# usb-hub-v0_3.net
KiCad netlist of a schematic drawn in EAGLE
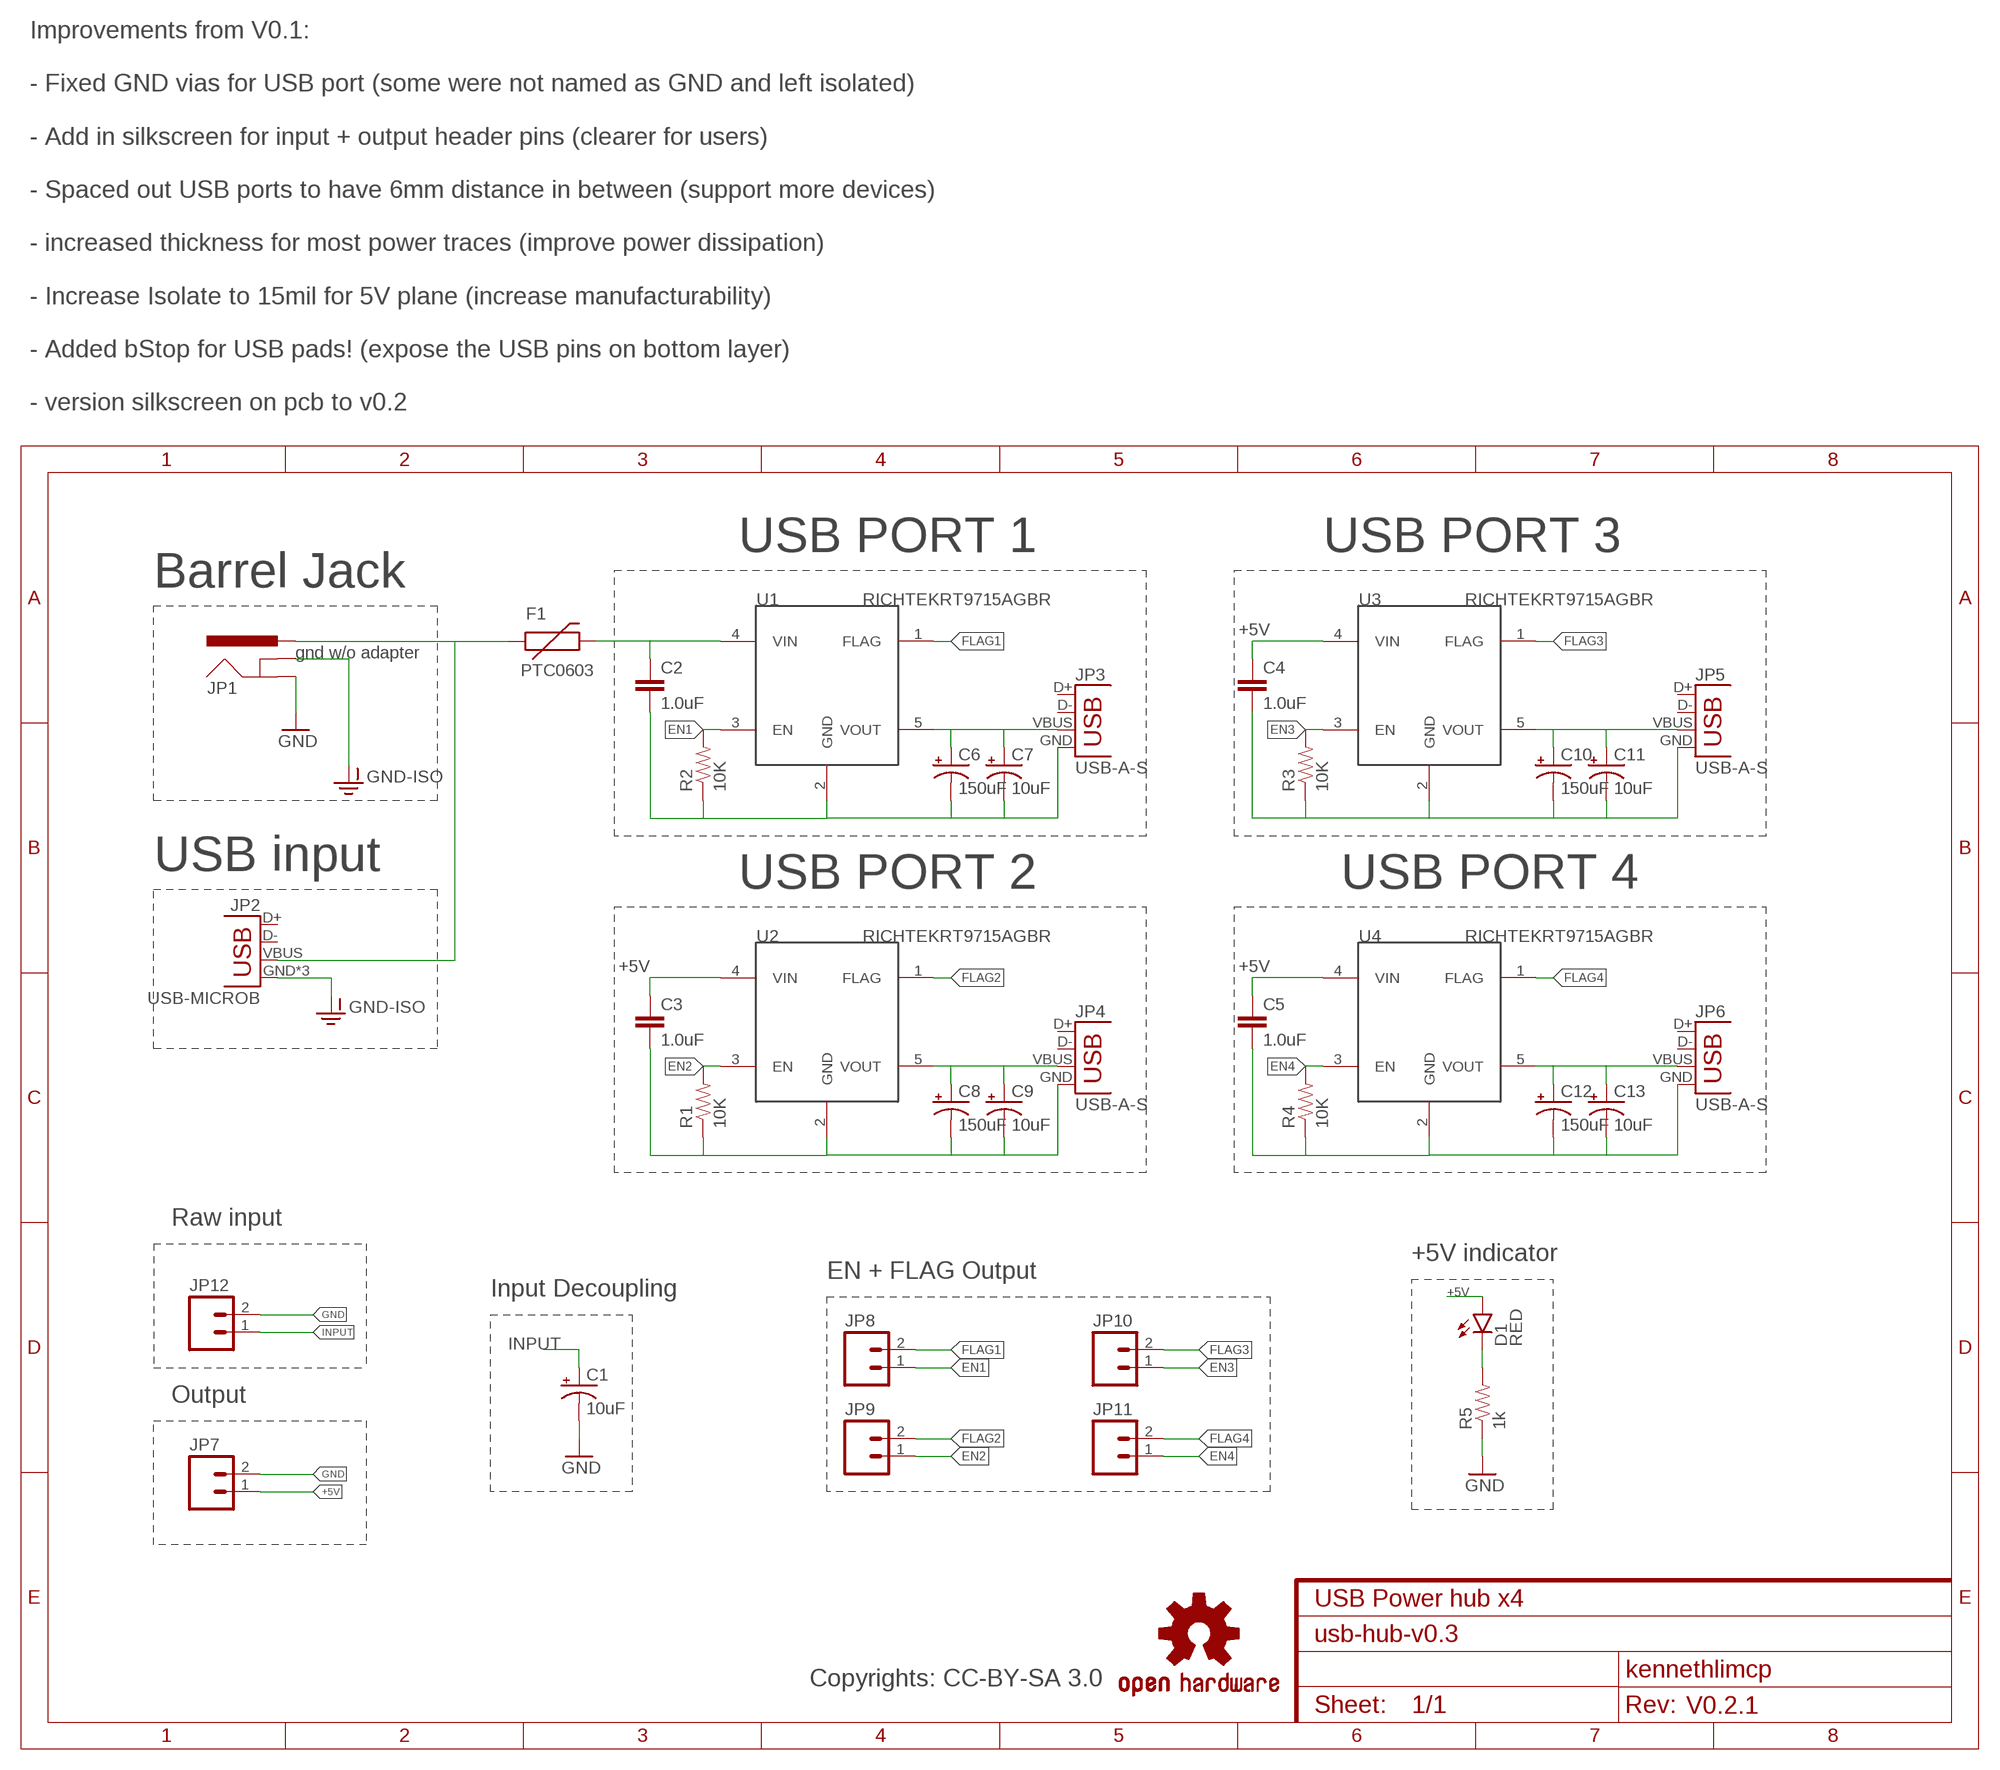
[diagram p0: schematic, sheet 1]

(export (version "E")
  (design (tool "Eeschema 10.0.6"))
  (components
    (comp (ref "C1")
      (value "10uF")
      (footprint "eagle-import:EIA3216")
      (libsource (lib "eagle-import") (part "10UF-16V-10%(TANT)"))
    )
    (comp (ref "C2")
      (value "1.0uF")
      (footprint "eagle-import:0603-CAP")
      (libsource (lib "eagle-import") (part "1.0UF-16V-10%(0603)"))
    )
    (comp (ref "C3")
      (value "1.0uF")
      (footprint "eagle-import:0603-CAP")
      (libsource (lib "eagle-import") (part "1.0UF-16V-10%(0603)"))
    )
    (comp (ref "C4")
      (value "1.0uF")
      (footprint "eagle-import:0603-CAP")
      (libsource (lib "eagle-import") (part "1.0UF-16V-10%(0603)"))
    )
    (comp (ref "C5")
      (value "1.0uF")
      (footprint "eagle-import:0603-CAP")
      (libsource (lib "eagle-import") (part "1.0UF-16V-10%(0603)"))
    )
    (comp (ref "C6")
      (value "150uF")
      (footprint "eagle-import:PANASONIC_D")
      (libsource (lib "eagle-import") (part "CAP_POLD"))
    )
    (comp (ref "C7")
      (value "10uF")
      (footprint "eagle-import:EIA3216")
      (libsource (lib "eagle-import") (part "10UF-16V-10%(TANT)"))
    )
    (comp (ref "C8")
      (value "150uF")
      (footprint "eagle-import:PANASONIC_D")
      (libsource (lib "eagle-import") (part "CAP_POLD"))
    )
    (comp (ref "C9")
      (value "10uF")
      (footprint "eagle-import:EIA3216")
      (libsource (lib "eagle-import") (part "10UF-16V-10%(TANT)"))
    )
    (comp (ref "C10")
      (value "150uF")
      (footprint "eagle-import:PANASONIC_D")
      (libsource (lib "eagle-import") (part "CAP_POLD"))
    )
    (comp (ref "C11")
      (value "10uF")
      (footprint "eagle-import:EIA3216")
      (libsource (lib "eagle-import") (part "10UF-16V-10%(TANT)"))
    )
    (comp (ref "C12")
      (value "150uF")
      (footprint "eagle-import:PANASONIC_D")
      (libsource (lib "eagle-import") (part "CAP_POLD"))
    )
    (comp (ref "C13")
      (value "10uF")
      (footprint "eagle-import:EIA3216")
      (libsource (lib "eagle-import") (part "10UF-16V-10%(TANT)"))
    )
    (comp (ref "D1")
      (value "RED")
      (footprint "eagle-import:LED-0603")
      (libsource (lib "eagle-import") (part "LED-RED0603"))
    )
    (comp (ref "F1")
      (value "PTC0603")
      (footprint "eagle-import:0603")
      (libsource (lib "eagle-import") (part "PTC0603"))
    )
    (comp (ref "JP1")
      (value "POWER_JACKPTH_LOCK")
      (footprint "eagle-import:POWER_JACK_PTH_LOCK")
      (libsource (lib "eagle-import") (part "POWER_JACKPTH_LOCK"))
    )
    (comp (ref "JP2")
      (value "USB-MICROB")
      (footprint "eagle-import:USB-MICROB")
      (libsource (lib "eagle-import") (part "USB-MICROB"))
    )
    (comp (ref "JP3")
      (value "USB-A-S")
      (footprint "eagle-import:USB-A-S")
      (libsource (lib "eagle-import") (part "USB-A-S"))
    )
    (comp (ref "JP4")
      (value "USB-A-S")
      (footprint "eagle-import:USB-A-S")
      (libsource (lib "eagle-import") (part "USB-A-S"))
    )
    (comp (ref "JP5")
      (value "USB-A-S")
      (footprint "eagle-import:USB-A-S")
      (libsource (lib "eagle-import") (part "USB-A-S"))
    )
    (comp (ref "JP6")
      (value "USB-A-S")
      (footprint "eagle-import:USB-A-S")
      (libsource (lib "eagle-import") (part "USB-A-S"))
    )
    (comp (ref "JP7")
      (value "M02PTH")
      (footprint "eagle-import:1X02")
      (libsource (lib "eagle-import") (part "M02PTH"))
    )
    (comp (ref "JP8")
      (value "M02PTH")
      (footprint "eagle-import:1X02")
      (libsource (lib "eagle-import") (part "M02PTH"))
    )
    (comp (ref "JP9")
      (value "M02PTH")
      (footprint "eagle-import:1X02")
      (libsource (lib "eagle-import") (part "M02PTH"))
    )
    (comp (ref "JP10")
      (value "M02PTH")
      (footprint "eagle-import:1X02")
      (libsource (lib "eagle-import") (part "M02PTH"))
    )
    (comp (ref "JP11")
      (value "M02PTH")
      (footprint "eagle-import:1X02")
      (libsource (lib "eagle-import") (part "M02PTH"))
    )
    (comp (ref "JP12")
      (value "M02PTH")
      (footprint "eagle-import:1X02")
      (libsource (lib "eagle-import") (part "M02PTH"))
    )
    (comp (ref "LOGO1")
      (value "OSHW-LOGOPAD")
      (footprint "eagle-import:OSHW-LOGO-M-PAD")
      (libsource (lib "eagle-import") (part "OSHW-LOGOPAD"))
    )
    (comp (ref "R1")
      (value "10K")
      (footprint "eagle-import:0402-RES")
      (libsource (lib "eagle-import") (part "RESISTOR0402"))
    )
    (comp (ref "R2")
      (value "10K")
      (footprint "eagle-import:0402-RES")
      (libsource (lib "eagle-import") (part "RESISTOR0402"))
    )
    (comp (ref "R3")
      (value "10K")
      (footprint "eagle-import:0402-RES")
      (libsource (lib "eagle-import") (part "RESISTOR0402"))
    )
    (comp (ref "R4")
      (value "10K")
      (footprint "eagle-import:0402-RES")
      (libsource (lib "eagle-import") (part "RESISTOR0402"))
    )
    (comp (ref "R5")
      (value "1k")
      (footprint "eagle-import:0402-RES")
      (libsource (lib "eagle-import") (part "RESISTOR0402"))
    )
    (comp (ref "U1")
      (value "RICHTEKRT9715AGBR")
      (footprint "eagle-import:SOT23-5")
      (libsource (lib "eagle-import") (part "RICHTEKRT9715AGBR"))
    )
    (comp (ref "U2")
      (value "RICHTEKRT9715AGBR")
      (footprint "eagle-import:SOT23-5")
      (libsource (lib "eagle-import") (part "RICHTEKRT9715AGBR"))
    )
    (comp (ref "U3")
      (value "RICHTEKRT9715AGBR")
      (footprint "eagle-import:SOT23-5")
      (libsource (lib "eagle-import") (part "RICHTEKRT9715AGBR"))
    )
    (comp (ref "U4")
      (value "RICHTEKRT9715AGBR")
      (footprint "eagle-import:SOT23-5")
      (libsource (lib "eagle-import") (part "RICHTEKRT9715AGBR"))
    )
  )
  (nets
    (net (code "1") (name "+5V") (class "Default")
      (node (ref "C2") (pin "1") (pinfunction "1_1") (pintype "passive"))
      (node (ref "C3") (pin "1") (pinfunction "1_1") (pintype "passive"))
      (node (ref "C4") (pin "1") (pinfunction "1_1") (pintype "passive"))
      (node (ref "C5") (pin "1") (pinfunction "1_1") (pintype "passive"))
      (node (ref "D1") (pin "A") (pinfunction "A_A") (pintype "passive"))
      (node (ref "F1") (pin "2") (pinfunction "2_2") (pintype "bidirectional"))
      (node (ref "JP7") (pin "1") (pinfunction "1_1") (pintype "passive"))
      (node (ref "U1") (pin "4") (pinfunction "VIN_4") (pintype "bidirectional"))
      (node (ref "U2") (pin "4") (pinfunction "VIN_4") (pintype "bidirectional"))
      (node (ref "U3") (pin "4") (pinfunction "VIN_4") (pintype "bidirectional"))
      (node (ref "U4") (pin "4") (pinfunction "VIN_4") (pintype "bidirectional"))
    )
    (net (code "2") (name "EN1") (class "Default")
      (node (ref "JP8") (pin "1") (pinfunction "1_1") (pintype "passive"))
      (node (ref "R2") (pin "2") (pinfunction "2_2") (pintype "passive"))
      (node (ref "U1") (pin "3") (pinfunction "EN_3") (pintype "bidirectional"))
    )
    (net (code "3") (name "EN2") (class "Default")
      (node (ref "JP9") (pin "1") (pinfunction "1_1") (pintype "passive"))
      (node (ref "R1") (pin "2") (pinfunction "2_2") (pintype "passive"))
      (node (ref "U2") (pin "3") (pinfunction "EN_3") (pintype "bidirectional"))
    )
    (net (code "4") (name "EN3") (class "Default")
      (node (ref "JP10") (pin "1") (pinfunction "1_1") (pintype "passive"))
      (node (ref "R3") (pin "2") (pinfunction "2_2") (pintype "passive"))
      (node (ref "U3") (pin "3") (pinfunction "EN_3") (pintype "bidirectional"))
    )
    (net (code "5") (name "EN4") (class "Default")
      (node (ref "JP11") (pin "1") (pinfunction "1_1") (pintype "passive"))
      (node (ref "R4") (pin "2") (pinfunction "2_2") (pintype "passive"))
      (node (ref "U4") (pin "3") (pinfunction "EN_3") (pintype "bidirectional"))
    )
    (net (code "6") (name "FLAG1") (class "Default")
      (node (ref "JP8") (pin "2") (pinfunction "2_2") (pintype "passive"))
      (node (ref "U1") (pin "1") (pinfunction "FLAG_1") (pintype "bidirectional"))
    )
    (net (code "7") (name "FLAG2") (class "Default")
      (node (ref "JP9") (pin "2") (pinfunction "2_2") (pintype "passive"))
      (node (ref "U2") (pin "1") (pinfunction "FLAG_1") (pintype "bidirectional"))
    )
    (net (code "8") (name "FLAG3") (class "Default")
      (node (ref "JP10") (pin "2") (pinfunction "2_2") (pintype "passive"))
      (node (ref "U3") (pin "1") (pinfunction "FLAG_1") (pintype "bidirectional"))
    )
    (net (code "9") (name "FLAG4") (class "Default")
      (node (ref "JP11") (pin "2") (pinfunction "2_2") (pintype "passive"))
      (node (ref "U4") (pin "1") (pinfunction "FLAG_1") (pintype "bidirectional"))
    )
    (net (code "10") (name "GND") (class "Default")
      (node (ref "C1") (pin "C") (pinfunction "-_C") (pintype "passive"))
      (node (ref "C10") (pin "-") (pinfunction "-_-") (pintype "passive"))
      (node (ref "C11") (pin "C") (pinfunction "-_C") (pintype "passive"))
      (node (ref "C12") (pin "-") (pinfunction "-_-") (pintype "passive"))
      (node (ref "C13") (pin "C") (pinfunction "-_C") (pintype "passive"))
      (node (ref "C2") (pin "2") (pinfunction "2_2") (pintype "passive"))
      (node (ref "C3") (pin "2") (pinfunction "2_2") (pintype "passive"))
      (node (ref "C4") (pin "2") (pinfunction "2_2") (pintype "passive"))
      (node (ref "C5") (pin "2") (pinfunction "2_2") (pintype "passive"))
      (node (ref "C6") (pin "-") (pinfunction "-_-") (pintype "passive"))
      (node (ref "C7") (pin "C") (pinfunction "-_C") (pintype "passive"))
      (node (ref "C8") (pin "-") (pinfunction "-_-") (pintype "passive"))
      (node (ref "C9") (pin "C") (pinfunction "-_C") (pintype "passive"))
      (node (ref "JP1") (pin "GND") (pinfunction "GND_GND") (pintype "bidirectional"))
      (node (ref "JP12") (pin "2") (pinfunction "2_2") (pintype "passive"))
      (node (ref "JP3") (pin "GND") (pinfunction "GND_GND") (pintype "bidirectional"))
      (node (ref "JP4") (pin "GND") (pinfunction "GND_GND") (pintype "bidirectional"))
      (node (ref "JP5") (pin "GND") (pinfunction "GND_GND") (pintype "bidirectional"))
      (node (ref "JP6") (pin "GND") (pinfunction "GND_GND") (pintype "bidirectional"))
      (node (ref "JP7") (pin "2") (pinfunction "2_2") (pintype "passive"))
      (node (ref "R1") (pin "1") (pinfunction "1_1") (pintype "passive"))
      (node (ref "R2") (pin "1") (pinfunction "1_1") (pintype "passive"))
      (node (ref "R3") (pin "1") (pinfunction "1_1") (pintype "passive"))
      (node (ref "R4") (pin "1") (pinfunction "1_1") (pintype "passive"))
      (node (ref "R5") (pin "1") (pinfunction "1_1") (pintype "passive"))
      (node (ref "U1") (pin "2") (pinfunction "GND_2") (pintype "bidirectional"))
      (node (ref "U2") (pin "2") (pinfunction "GND_2") (pintype "bidirectional"))
      (node (ref "U3") (pin "2") (pinfunction "GND_2") (pintype "bidirectional"))
      (node (ref "U4") (pin "2") (pinfunction "GND_2") (pintype "bidirectional"))
    )
    (net (code "11") (name "GND-ISO") (class "Default")
      (node (ref "JP1") (pin "GNDBREAK") (pinfunction "GNDBREAK_GNDBREAK") (pintype "bidirectional"))
      (node (ref "JP2") (pin "GND") (pinfunction "GND_GND") (pintype "bidirectional"))
      (node (ref "JP2") (pin "MT1") (pinfunction "GND_MT1") (pintype "bidirectional"))
      (node (ref "JP2") (pin "MT2") (pinfunction "GND_MT2") (pintype "bidirectional"))
    )
    (net (code "12") (name "INPUT") (class "Default")
      (node (ref "C1") (pin "A") (pinfunction "+_A") (pintype "passive"))
      (node (ref "F1") (pin "1") (pinfunction "1_1") (pintype "bidirectional"))
      (node (ref "JP1") (pin "PWR") (pinfunction "PWR_PWR") (pintype "bidirectional"))
      (node (ref "JP12") (pin "1") (pinfunction "1_1") (pintype "passive"))
      (node (ref "JP2") (pin "VBUS") (pinfunction "VBUS_VBUS") (pintype "bidirectional"))
    )
    (net (code "13") (name "Net-(C7-+)") (class "Default")
      (node (ref "C6") (pin "+") (pinfunction "+_+") (pintype "passive"))
      (node (ref "C7") (pin "A") (pinfunction "+_A") (pintype "passive"))
      (node (ref "JP3") (pin "VBUS") (pinfunction "VBUS_VBUS") (pintype "bidirectional"))
      (node (ref "U1") (pin "5") (pinfunction "VOUT_5") (pintype "bidirectional"))
    )
    (net (code "14") (name "Net-(C9-+)") (class "Default")
      (node (ref "C8") (pin "+") (pinfunction "+_+") (pintype "passive"))
      (node (ref "C9") (pin "A") (pinfunction "+_A") (pintype "passive"))
      (node (ref "JP4") (pin "VBUS") (pinfunction "VBUS_VBUS") (pintype "bidirectional"))
      (node (ref "U2") (pin "5") (pinfunction "VOUT_5") (pintype "bidirectional"))
    )
    (net (code "15") (name "Net-(C11-+)") (class "Default")
      (node (ref "C10") (pin "+") (pinfunction "+_+") (pintype "passive"))
      (node (ref "C11") (pin "A") (pinfunction "+_A") (pintype "passive"))
      (node (ref "JP5") (pin "VBUS") (pinfunction "VBUS_VBUS") (pintype "bidirectional"))
      (node (ref "U3") (pin "5") (pinfunction "VOUT_5") (pintype "bidirectional"))
    )
    (net (code "16") (name "Net-(C13-+)") (class "Default")
      (node (ref "C12") (pin "+") (pinfunction "+_+") (pintype "passive"))
      (node (ref "C13") (pin "A") (pinfunction "+_A") (pintype "passive"))
      (node (ref "JP6") (pin "VBUS") (pinfunction "VBUS_VBUS") (pintype "bidirectional"))
      (node (ref "U4") (pin "5") (pinfunction "VOUT_5") (pintype "bidirectional"))
    )
    (net (code "17") (name "Net-(D1-PadC)") (class "Default")
      (node (ref "D1") (pin "C") (pinfunction "C_C") (pintype "passive"))
      (node (ref "R5") (pin "2") (pinfunction "2_2") (pintype "passive"))
    )
    (net (code "18") (name "unconnected-(JP2-PadD+)") (class "Default")
      (node (ref "JP2") (pin "D+") (pinfunction "D+_D+") (pintype "bidirectional"))
    )
    (net (code "19") (name "unconnected-(JP2-PadD-)") (class "Default")
      (node (ref "JP2") (pin "D-") (pinfunction "D-_D-") (pintype "bidirectional"))
    )
    (net (code "20") (name "unconnected-(JP3-PadD+)") (class "Default")
      (node (ref "JP3") (pin "D+") (pinfunction "D+_D+") (pintype "bidirectional"))
    )
    (net (code "21") (name "unconnected-(JP3-PadD-)") (class "Default")
      (node (ref "JP3") (pin "D-") (pinfunction "D-_D-") (pintype "bidirectional"))
    )
    (net (code "22") (name "unconnected-(JP4-PadD+)") (class "Default")
      (node (ref "JP4") (pin "D+") (pinfunction "D+_D+") (pintype "bidirectional"))
    )
    (net (code "23") (name "unconnected-(JP4-PadD-)") (class "Default")
      (node (ref "JP4") (pin "D-") (pinfunction "D-_D-") (pintype "bidirectional"))
    )
    (net (code "24") (name "unconnected-(JP5-PadD+)") (class "Default")
      (node (ref "JP5") (pin "D+") (pinfunction "D+_D+") (pintype "bidirectional"))
    )
    (net (code "25") (name "unconnected-(JP5-PadD-)") (class "Default")
      (node (ref "JP5") (pin "D-") (pinfunction "D-_D-") (pintype "bidirectional"))
    )
    (net (code "26") (name "unconnected-(JP6-PadD+)") (class "Default")
      (node (ref "JP6") (pin "D+") (pinfunction "D+_D+") (pintype "bidirectional"))
    )
    (net (code "27") (name "unconnected-(JP6-PadD-)") (class "Default")
      (node (ref "JP6") (pin "D-") (pinfunction "D-_D-") (pintype "bidirectional"))
    )
  )
)
